# ExenMiniBatteryShield.net
KiCad netlist of a schematic drawn in EAGLE
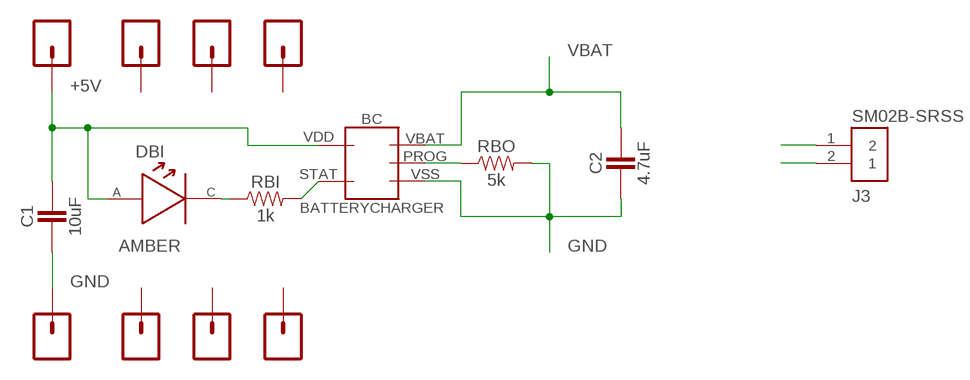
[diagram p0: schematic, sheet 1]

(export (version "E")
  (design (tool "Eeschema 10.0.6"))
  (components
    (comp (ref "+3.3")
      (value "CONN_01PTH_NO_SILK_YES_STOP")
      (footprint "eagle-import:1X01_NO_SILK")
      (libsource (lib "eagle-import") (part "CONN_01PTH_NO_SILK_YES_STOP"))
    )
    (comp (ref "+5")
      (value "CONN_01PTH_NO_SILK_YES_STOP")
      (footprint "eagle-import:1X01_NO_SILK")
      (libsource (lib "eagle-import") (part "CONN_01PTH_NO_SILK_YES_STOP"))
    )
    (comp (ref "A1")
      (value "CONN_01PTH_NO_SILK_YES_STOP")
      (footprint "eagle-import:1X01_NO_SILK")
      (libsource (lib "eagle-import") (part "CONN_01PTH_NO_SILK_YES_STOP"))
    )
    (comp (ref "A2")
      (value "CONN_01PTH_NO_SILK_YES_STOP")
      (footprint "eagle-import:1X01_NO_SILK")
      (libsource (lib "eagle-import") (part "CONN_01PTH_NO_SILK_YES_STOP"))
    )
    (comp (ref "BC")
      (value "BATTERYCHARGER")
      (footprint "eagle-import:SOT-753")
      (libsource (lib "eagle-import") (part "BATTERYCHARGER"))
    )
    (comp (ref "C1")
      (value "10uF")
      (footprint "eagle-import:PASSIVE-0603")
      (libsource (lib "eagle-import") (part "CAPACITOR"))
    )
    (comp (ref "C2")
      (value "4.7uF")
      (footprint "eagle-import:PASSIVE-0603")
      (libsource (lib "eagle-import") (part "CAPACITOR"))
    )
    (comp (ref "DBI")
      (value "AMBER")
      (footprint "eagle-import:PASSIVE-0603")
      (libsource (lib "eagle-import") (part "DIODE"))
    )
    (comp (ref "GND")
      (value "CONN_01PTH_NO_SILK_YES_STOP")
      (footprint "eagle-import:1X01_NO_SILK")
      (libsource (lib "eagle-import") (part "CONN_01PTH_NO_SILK_YES_STOP"))
    )
    (comp (ref "J3")
      (value "SM02B-SRSS")
      (footprint "eagle-import:JST_SH_2X1")
      (fields (field (name "PARTNO") "AS-ITM-00231"))
      (libsource (lib "eagle-import") (part "AS-ITM-00231"))
    )
    (comp (ref "RBI")
      (value "1k")
      (footprint "eagle-import:PASSIVE-0603")
      (libsource (lib "eagle-import") (part "RESISTOR"))
    )
    (comp (ref "RBO")
      (value "5k")
      (footprint "eagle-import:PASSIVE-0603")
      (libsource (lib "eagle-import") (part "RESISTOR"))
    )
    (comp (ref "RST")
      (value "CONN_01PTH_NO_SILK_YES_STOP")
      (footprint "eagle-import:1X01_NO_SILK")
      (libsource (lib "eagle-import") (part "CONN_01PTH_NO_SILK_YES_STOP"))
    )
    (comp (ref "SCL")
      (value "CONN_01PTH_NO_SILK_YES_STOP")
      (footprint "eagle-import:1X01_NO_SILK")
      (libsource (lib "eagle-import") (part "CONN_01PTH_NO_SILK_YES_STOP"))
    )
    (comp (ref "SDA")
      (value "CONN_01PTH_NO_SILK_YES_STOP")
      (footprint "eagle-import:1X01_NO_SILK")
      (libsource (lib "eagle-import") (part "CONN_01PTH_NO_SILK_YES_STOP"))
    )
  )
  (nets
    (net (code "1") (name "/+5V") (class "Default")
      (node (ref "+5") (pin "1") (pinfunction "1_1") (pintype "passive"))
      (node (ref "BC") (pin "VDD") (pinfunction "VDD_VDD") (pintype "bidirectional"))
      (node (ref "C1") (pin "2") (pinfunction "2_2") (pintype "passive"))
      (node (ref "DBI") (pin "1") (pinfunction "ANODE_1") (pintype "bidirectional"))
    )
    (net (code "2") (name "/GND") (class "Default")
      (node (ref "BC") (pin "VSS") (pinfunction "VSS_VSS") (pintype "bidirectional"))
      (node (ref "C1") (pin "1") (pinfunction "1_1") (pintype "passive"))
      (node (ref "C2") (pin "1") (pinfunction "1_1") (pintype "passive"))
      (node (ref "GND") (pin "1") (pinfunction "1_1") (pintype "passive"))
      (node (ref "J3") (pin "1") (pinfunction "2_1") (pintype "bidirectional"))
      (node (ref "RBO") (pin "2") (pinfunction "2_2") (pintype "passive"))
    )
    (net (code "3") (name "/VBAT") (class "Default")
      (node (ref "BC") (pin "VBAT") (pinfunction "VBAT_VBAT") (pintype "bidirectional"))
      (node (ref "C2") (pin "2") (pinfunction "2_2") (pintype "passive"))
      (node (ref "J3") (pin "2") (pinfunction "1_2") (pintype "bidirectional"))
    )
    (net (code "4") (name "Net-(BC-PadPROG)") (class "Default")
      (node (ref "BC") (pin "PROG") (pinfunction "PROG_PROG") (pintype "bidirectional"))
      (node (ref "RBO") (pin "1") (pinfunction "1_1") (pintype "passive"))
    )
    (net (code "5") (name "Net-(BC-PadSTAT)") (class "Default")
      (node (ref "BC") (pin "STAT") (pinfunction "STAT_STAT") (pintype "bidirectional"))
      (node (ref "RBI") (pin "2") (pinfunction "2_2") (pintype "passive"))
    )
    (net (code "6") (name "Net-(DBI-CATHODE)") (class "Default")
      (node (ref "DBI") (pin "2") (pinfunction "CATHODE_2") (pintype "bidirectional"))
      (node (ref "RBI") (pin "1") (pinfunction "1_1") (pintype "passive"))
    )
    (net (code "7") (name "unconnected-(+3.3-Pad1)") (class "Default")
      (node (ref "+3.3") (pin "1") (pinfunction "1_1") (pintype "passive"))
    )
    (net (code "8") (name "unconnected-(A1-Pad1)") (class "Default")
      (node (ref "A1") (pin "1") (pinfunction "1_1") (pintype "passive"))
    )
    (net (code "9") (name "unconnected-(A2-Pad1)") (class "Default")
      (node (ref "A2") (pin "1") (pinfunction "1_1") (pintype "passive"))
    )
    (net (code "10") (name "unconnected-(RST-Pad1)") (class "Default")
      (node (ref "RST") (pin "1") (pinfunction "1_1") (pintype "passive"))
    )
    (net (code "11") (name "unconnected-(SCL-Pad1)") (class "Default")
      (node (ref "SCL") (pin "1") (pinfunction "1_1") (pintype "passive"))
    )
    (net (code "12") (name "unconnected-(SDA-Pad1)") (class "Default")
      (node (ref "SDA") (pin "1") (pinfunction "1_1") (pintype "passive"))
    )
  )
)
